# wifi_lora_gw_v1_1.net
KiCad netlist of a schematic drawn in EAGLE
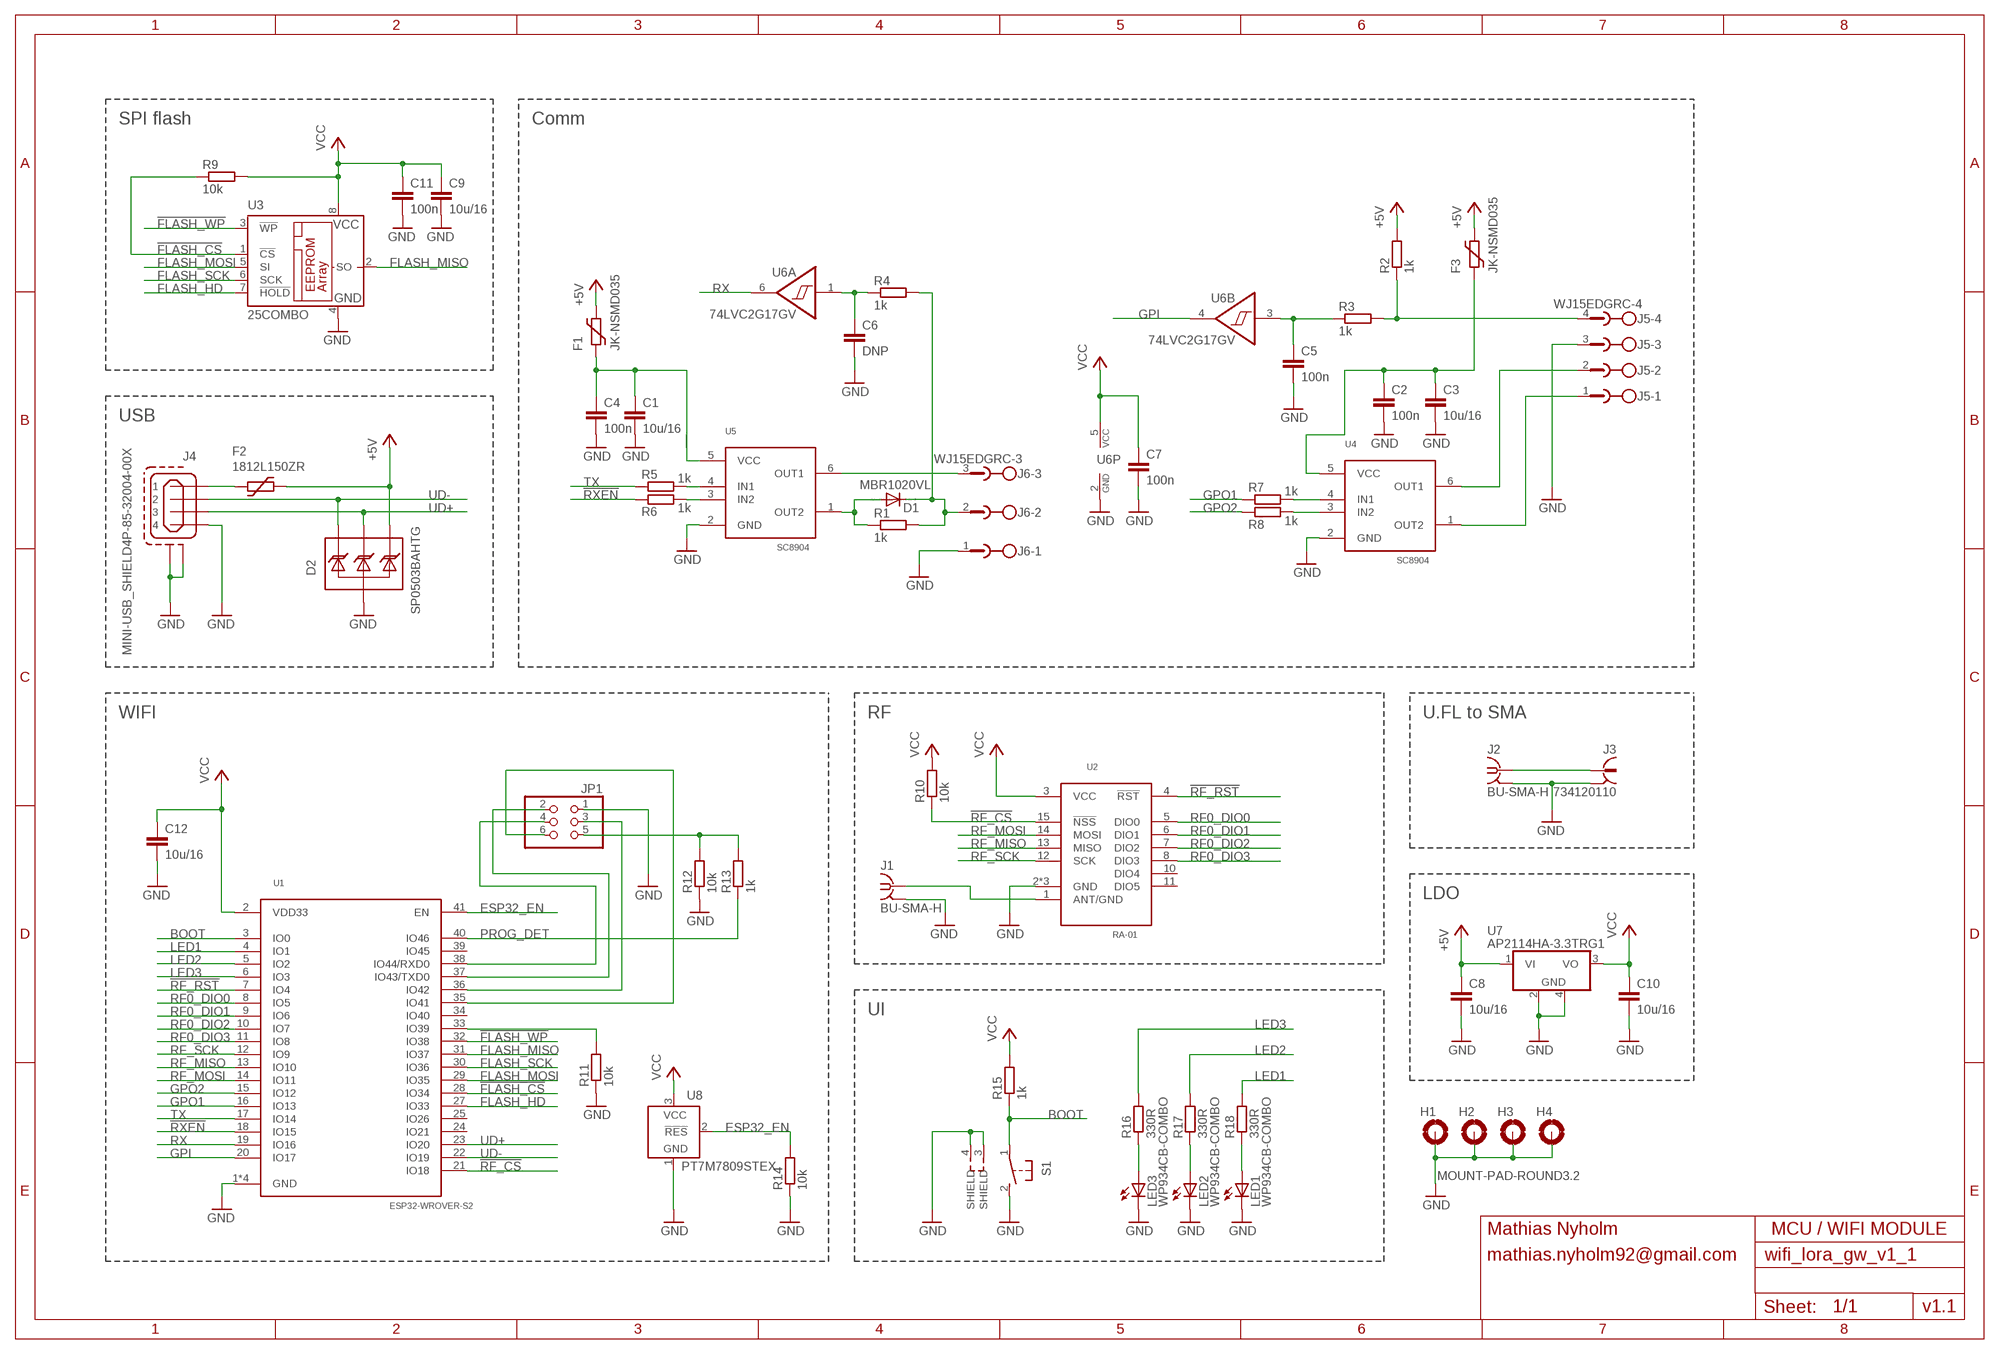
[diagram p0: schematic, sheet 1]

(export (version "E")
  (design (tool "Eeschema 10.0.6"))
  (components
    (comp (ref "C1")
      (value "10u/16")
      (footprint "eagle-import:C1206")
      (libsource (lib "eagle-import") (part "C-EUC1206"))
    )
    (comp (ref "C2")
      (value "100n")
      (footprint "eagle-import:C0805")
      (libsource (lib "eagle-import") (part "C-EUC0805"))
    )
    (comp (ref "C3")
      (value "10u/16")
      (footprint "eagle-import:C1206")
      (libsource (lib "eagle-import") (part "C-EUC1206"))
    )
    (comp (ref "C4")
      (value "100n")
      (footprint "eagle-import:C0805")
      (libsource (lib "eagle-import") (part "C-EUC0805"))
    )
    (comp (ref "C5")
      (value "100n")
      (footprint "eagle-import:C0805")
      (libsource (lib "eagle-import") (part "C-EUC0805"))
    )
    (comp (ref "C6")
      (value "DNP")
      (footprint "eagle-import:C0805")
      (libsource (lib "eagle-import") (part "C-EUC0805"))
    )
    (comp (ref "C7")
      (value "100n")
      (footprint "eagle-import:C0805")
      (libsource (lib "eagle-import") (part "C-EUC0805"))
    )
    (comp (ref "C8")
      (value "10u/16")
      (footprint "eagle-import:C1206")
      (libsource (lib "eagle-import") (part "C-EUC1206"))
    )
    (comp (ref "C9")
      (value "10u/16")
      (footprint "eagle-import:C1206")
      (libsource (lib "eagle-import") (part "C-EUC1206"))
    )
    (comp (ref "C10")
      (value "10u/16")
      (footprint "eagle-import:C1206")
      (libsource (lib "eagle-import") (part "C-EUC1206"))
    )
    (comp (ref "C11")
      (value "100n")
      (footprint "eagle-import:C0805")
      (libsource (lib "eagle-import") (part "C-EUC0805"))
    )
    (comp (ref "C12")
      (value "10u/16")
      (footprint "eagle-import:C1206")
      (libsource (lib "eagle-import") (part "C-EUC1206"))
    )
    (comp (ref "D1")
      (value "MBR1020VL")
      (footprint "eagle-import:SOD123")
      (libsource (lib "eagle-import") (part "DIODE-SOD123"))
    )
    (comp (ref "D2")
      (value "SP0503BAHTG")
      (footprint "eagle-import:SOT143")
      (libsource (lib "eagle-import") (part "SP0503BAHTG"))
    )
    (comp (ref "F1")
      (value "JK-NSMD035")
      (footprint "eagle-import:1206L")
      (libsource (lib "eagle-import") (part "1206L"))
    )
    (comp (ref "F2")
      (value "1812L150ZR")
      (footprint "eagle-import:1812L")
      (libsource (lib "eagle-import") (part "1812L"))
    )
    (comp (ref "F3")
      (value "JK-NSMD035")
      (footprint "eagle-import:1206L")
      (libsource (lib "eagle-import") (part "1206L"))
    )
    (comp (ref "H1")
      (value "MOUNT-PAD-ROUND3.2")
      (footprint "eagle-import:3,2-PAD")
      (libsource (lib "eagle-import") (part "MOUNT-PAD-ROUND3.2"))
    )
    (comp (ref "H2")
      (value "MOUNT-PAD-ROUND3.2")
      (footprint "eagle-import:3,2-PAD")
      (libsource (lib "eagle-import") (part "MOUNT-PAD-ROUND3.2"))
    )
    (comp (ref "H3")
      (value "MOUNT-PAD-ROUND3.2")
      (footprint "eagle-import:3,2-PAD")
      (libsource (lib "eagle-import") (part "MOUNT-PAD-ROUND3.2"))
    )
    (comp (ref "H4")
      (value "MOUNT-PAD-ROUND3.2")
      (footprint "eagle-import:3,2-PAD")
      (libsource (lib "eagle-import") (part "MOUNT-PAD-ROUND3.2"))
    )
    (comp (ref "J1")
      (value "BU-SMA-H")
      (footprint "eagle-import:BU-SMA-H")
      (libsource (lib "eagle-import") (part "BU-SMA-H"))
    )
    (comp (ref "J2")
      (value "BU-SMA-H")
      (footprint "eagle-import:BU-SMA-H")
      (libsource (lib "eagle-import") (part "BU-SMA-H"))
    )
    (comp (ref "J3")
      (value "734120110")
      (footprint "eagle-import:734120110")
      (libsource (lib "eagle-import") (part "734120110"))
    )
    (comp (ref "J4")
      (value "MINI-USB_SHIELD4P-85-32004-00X")
      (footprint "eagle-import:85-32004-00X")
      (libsource (lib "eagle-import") (part "MINI-USB_SHIELD4P-85-32004-00X"))
    )
    (comp (ref "J5")
      (value "WJ15EDGRC-4")
      (footprint "eagle-import:WJ15EDGRC-3.81-4")
      (libsource (lib "eagle-import") (part "WJ15EDGRC-4"))
    )
    (comp (ref "J6")
      (value "WJ15EDGRC-3")
      (footprint "eagle-import:WJ15EDGRC-3.81-3")
      (libsource (lib "eagle-import") (part "WJ15EDGRC-3"))
    )
    (comp (ref "JP1")
      (value "PINHD-2X3")
      (footprint "eagle-import:2X03")
      (libsource (lib "eagle-import") (part "PINHD-2X3"))
    )
    (comp (ref "LED1")
      (value "WP934CB-COMBO")
      (footprint "eagle-import:WP934CB-COMBO")
      (libsource (lib "eagle-import") (part "WP934CB-COMBO"))
    )
    (comp (ref "LED2")
      (value "WP934CB-COMBO")
      (footprint "eagle-import:WP934CB-COMBO")
      (libsource (lib "eagle-import") (part "WP934CB-COMBO"))
    )
    (comp (ref "LED3")
      (value "WP934CB-COMBO")
      (footprint "eagle-import:WP934CB-COMBO")
      (libsource (lib "eagle-import") (part "WP934CB-COMBO"))
    )
    (comp (ref "R1")
      (value "1k")
      (footprint "eagle-import:R0805")
      (libsource (lib "eagle-import") (part "R-EU_R0805"))
    )
    (comp (ref "R2")
      (value "1k")
      (footprint "eagle-import:R0805")
      (libsource (lib "eagle-import") (part "R-EU_R0805"))
    )
    (comp (ref "R3")
      (value "1k")
      (footprint "eagle-import:R0805")
      (libsource (lib "eagle-import") (part "R-EU_R0805"))
    )
    (comp (ref "R4")
      (value "1k")
      (footprint "eagle-import:R0805")
      (libsource (lib "eagle-import") (part "R-EU_R0805"))
    )
    (comp (ref "R5")
      (value "1k")
      (footprint "eagle-import:R0805")
      (libsource (lib "eagle-import") (part "R-EU_R0805"))
    )
    (comp (ref "R6")
      (value "1k")
      (footprint "eagle-import:R0805")
      (libsource (lib "eagle-import") (part "R-EU_R0805"))
    )
    (comp (ref "R7")
      (value "1k")
      (footprint "eagle-import:R0805")
      (libsource (lib "eagle-import") (part "R-EU_R0805"))
    )
    (comp (ref "R8")
      (value "1k")
      (footprint "eagle-import:R0805")
      (libsource (lib "eagle-import") (part "R-EU_R0805"))
    )
    (comp (ref "R9")
      (value "10k")
      (footprint "eagle-import:R0805")
      (libsource (lib "eagle-import") (part "R-EU_R0805"))
    )
    (comp (ref "R10")
      (value "10k")
      (footprint "eagle-import:R0805")
      (libsource (lib "eagle-import") (part "R-EU_R0805"))
    )
    (comp (ref "R11")
      (value "10k")
      (footprint "eagle-import:R0805")
      (libsource (lib "eagle-import") (part "R-EU_R0805"))
    )
    (comp (ref "R12")
      (value "10k")
      (footprint "eagle-import:R0805")
      (libsource (lib "eagle-import") (part "R-EU_R0805"))
    )
    (comp (ref "R13")
      (value "1k")
      (footprint "eagle-import:R0805")
      (libsource (lib "eagle-import") (part "R-EU_R0805"))
    )
    (comp (ref "R14")
      (value "10k")
      (footprint "eagle-import:R0805")
      (libsource (lib "eagle-import") (part "R-EU_R0805"))
    )
    (comp (ref "R15")
      (value "1k")
      (footprint "eagle-import:R0805")
      (libsource (lib "eagle-import") (part "R-EU_R0805"))
    )
    (comp (ref "R16")
      (value "330R")
      (footprint "eagle-import:R0805")
      (libsource (lib "eagle-import") (part "R-EU_R0805"))
    )
    (comp (ref "R17")
      (value "330R")
      (footprint "eagle-import:R0805")
      (libsource (lib "eagle-import") (part "R-EU_R0805"))
    )
    (comp (ref "R18")
      (value "330R")
      (footprint "eagle-import:R0805")
      (libsource (lib "eagle-import") (part "R-EU_R0805"))
    )
    (comp (ref "S1")
      (value "31-XX")
      (footprint "eagle-import:B3F-31XX")
      (libsource (lib "eagle-import") (part "31-XX"))
    )
    (comp (ref "U1")
      (value "ESP32-WROVER-S2")
      (footprint "eagle-import:ESP32-WROVER-I-S2")
      (libsource (lib "eagle-import") (part "ESP32-WROVER-S2"))
    )
    (comp (ref "U2")
      (value "RA-01")
      (footprint "eagle-import:RA-02")
      (libsource (lib "eagle-import") (part "RA-02"))
    )
    (comp (ref "U3")
      (value "25COMBO")
      (footprint "eagle-import:SO-08M-COMBO")
      (libsource (lib "eagle-import") (part "25COMBO"))
    )
    (comp (ref "U4")
      (value "SC8904")
      (footprint "eagle-import:SOT23-6L")
      (libsource (lib "eagle-import") (part "SC8904"))
    )
    (comp (ref "U5")
      (value "SC8904")
      (footprint "eagle-import:SOT23-6L")
      (libsource (lib "eagle-import") (part "SC8904"))
    )
    (comp (ref "U6")
      (value "74LVC2G17GV")
      (footprint "eagle-import:SOT23-6L")
      (libsource (lib "eagle-import") (part "74LVC2G17GV"))
    )
    (comp (ref "U7")
      (value "AP2114HA-3.3TRG1")
      (footprint "eagle-import:SOT223")
      (libsource (lib "eagle-import") (part "MCP1754-DB"))
    )
    (comp (ref "U8")
      (value "PT7M7809STEX")
      (footprint "eagle-import:SOT23B-3")
      (libsource (lib "eagle-import") (part "APX809S-SA"))
    )
  )
  (nets
    (net (code "1") (name "+5V") (class "Default")
      (node (ref "C8") (pin "1") (pinfunction "1_1") (pintype "passive"))
      (node (ref "D2") (pin "4") (pinfunction "C3_4") (pintype "passive"))
      (node (ref "F1") (pin "P$2") (pinfunction "2_P$2") (pintype "passive"))
      (node (ref "F2") (pin "P$2") (pinfunction "2_P$2") (pintype "passive"))
      (node (ref "F3") (pin "P$2") (pinfunction "2_P$2") (pintype "passive"))
      (node (ref "R2") (pin "2") (pinfunction "2_2") (pintype "passive"))
      (node (ref "U7") (pin "1") (pinfunction "VI_1") (pintype "input"))
    )
    (net (code "2") (name "/BOOT") (class "Default")
      (node (ref "R15") (pin "1") (pinfunction "1_1") (pintype "passive"))
      (node (ref "S1") (pin "1") (pinfunction "P_1") (pintype "passive"))
      (node (ref "U1") (pin "3") (pinfunction "IO0_3") (pintype "bidirectional"))
    )
    (net (code "3") (name "/ESP32_EN") (class "Default")
      (node (ref "R14") (pin "2") (pinfunction "2_2") (pintype "passive"))
      (node (ref "U1") (pin "41") (pinfunction "EN_41") (pintype "bidirectional"))
      (node (ref "U8") (pin "2") (pinfunction "~{RES}_2") (pintype "output"))
    )
    (net (code "4") (name "/FLASH_HD") (class "Default")
      (node (ref "U1") (pin "27") (pinfunction "IO33_27") (pintype "bidirectional"))
      (node (ref "U3") (pin "7") (pinfunction "~{HOLD}_7") (pintype "input"))
    )
    (net (code "5") (name "/FLASH_MISO") (class "Default")
      (node (ref "U1") (pin "31") (pinfunction "IO37_31") (pintype "bidirectional"))
      (node (ref "U3") (pin "2") (pinfunction "SO_2") (pintype "bidirectional"))
    )
    (net (code "6") (name "/FLASH_MOSI") (class "Default")
      (node (ref "U1") (pin "29") (pinfunction "IO35_29") (pintype "bidirectional"))
      (node (ref "U3") (pin "5") (pinfunction "SI_5") (pintype "input"))
    )
    (net (code "7") (name "/FLASH_SCK") (class "Default")
      (node (ref "U1") (pin "30") (pinfunction "IO36_30") (pintype "bidirectional"))
      (node (ref "U3") (pin "6") (pinfunction "SCK_6") (pintype "input"))
    )
    (net (code "8") (name "/GPI") (class "Default")
      (node (ref "U1") (pin "20") (pinfunction "IO17_20") (pintype "bidirectional"))
      (node (ref "U6") (pin "4") (pinfunction "O_4") (pintype "output"))
    )
    (net (code "9") (name "/GPO1") (class "Default")
      (node (ref "R7") (pin "1") (pinfunction "1_1") (pintype "passive"))
      (node (ref "U1") (pin "16") (pinfunction "IO13_16") (pintype "bidirectional"))
    )
    (net (code "10") (name "/GPO2") (class "Default")
      (node (ref "R8") (pin "1") (pinfunction "1_1") (pintype "passive"))
      (node (ref "U1") (pin "15") (pinfunction "IO12_15") (pintype "bidirectional"))
    )
    (net (code "11") (name "/LED1") (class "Default")
      (node (ref "R18") (pin "2") (pinfunction "2_2") (pintype "passive"))
      (node (ref "U1") (pin "4") (pinfunction "IO1_4") (pintype "bidirectional"))
    )
    (net (code "12") (name "/LED2") (class "Default")
      (node (ref "R17") (pin "2") (pinfunction "2_2") (pintype "passive"))
      (node (ref "U1") (pin "5") (pinfunction "IO2_5") (pintype "bidirectional"))
    )
    (net (code "13") (name "/LED3") (class "Default")
      (node (ref "R16") (pin "2") (pinfunction "2_2") (pintype "passive"))
      (node (ref "U1") (pin "6") (pinfunction "IO3_6") (pintype "bidirectional"))
    )
    (net (code "14") (name "/PROG_DET") (class "Default")
      (node (ref "R13") (pin "1") (pinfunction "1_1") (pintype "passive"))
      (node (ref "U1") (pin "40") (pinfunction "IO46_40") (pintype "bidirectional"))
    )
    (net (code "15") (name "/RF0_DIO0") (class "Default")
      (node (ref "U1") (pin "8") (pinfunction "IO5_8") (pintype "bidirectional"))
      (node (ref "U2") (pin "5") (pinfunction "DIO0_5") (pintype "bidirectional"))
    )
    (net (code "16") (name "/RF0_DIO1") (class "Default")
      (node (ref "U1") (pin "9") (pinfunction "IO6_9") (pintype "bidirectional"))
      (node (ref "U2") (pin "6") (pinfunction "DIO1_6") (pintype "bidirectional"))
    )
    (net (code "17") (name "/RF0_DIO2") (class "Default")
      (node (ref "U1") (pin "10") (pinfunction "IO7_10") (pintype "bidirectional"))
      (node (ref "U2") (pin "7") (pinfunction "DIO2_7") (pintype "bidirectional"))
    )
    (net (code "18") (name "/RF0_DIO3") (class "Default")
      (node (ref "U1") (pin "11") (pinfunction "IO8_11") (pintype "bidirectional"))
      (node (ref "U2") (pin "8") (pinfunction "DIO3_8") (pintype "bidirectional"))
    )
    (net (code "19") (name "/RF_MISO") (class "Default")
      (node (ref "U1") (pin "13") (pinfunction "IO10_13") (pintype "bidirectional"))
      (node (ref "U2") (pin "13") (pinfunction "MISO_13") (pintype "bidirectional"))
    )
    (net (code "20") (name "/RF_MOSI") (class "Default")
      (node (ref "U1") (pin "14") (pinfunction "IO11_14") (pintype "bidirectional"))
      (node (ref "U2") (pin "14") (pinfunction "MOSI_14") (pintype "bidirectional"))
    )
    (net (code "21") (name "/RF_SCK") (class "Default")
      (node (ref "U1") (pin "12") (pinfunction "IO9_12") (pintype "bidirectional"))
      (node (ref "U2") (pin "12") (pinfunction "SCK_12") (pintype "bidirectional"))
    )
    (net (code "22") (name "/RX") (class "Default")
      (node (ref "U1") (pin "19") (pinfunction "IO16_19") (pintype "bidirectional"))
      (node (ref "U6") (pin "6") (pinfunction "O_6") (pintype "output"))
    )
    (net (code "23") (name "/TX") (class "Default")
      (node (ref "R5") (pin "1") (pinfunction "1_1") (pintype "passive"))
      (node (ref "U1") (pin "17") (pinfunction "IO14_17") (pintype "bidirectional"))
    )
    (net (code "24") (name "/UD+") (class "Default")
      (node (ref "D2") (pin "3") (pinfunction "C2_3") (pintype "passive"))
      (node (ref "J4") (pin "3") (pinfunction "3_3") (pintype "passive"))
      (node (ref "U1") (pin "23") (pinfunction "IO20_23") (pintype "bidirectional"))
    )
    (net (code "25") (name "/UD-") (class "Default")
      (node (ref "D2") (pin "2") (pinfunction "C1_2") (pintype "passive"))
      (node (ref "J4") (pin "2") (pinfunction "2_2") (pintype "passive"))
      (node (ref "U1") (pin "22") (pinfunction "IO19_22") (pintype "bidirectional"))
    )
    (net (code "26") (name "/~{FLASH_CS}") (class "Default")
      (node (ref "R9") (pin "1") (pinfunction "1_1") (pintype "passive"))
      (node (ref "U1") (pin "28") (pinfunction "IO34_28") (pintype "bidirectional"))
      (node (ref "U3") (pin "1") (pinfunction "~{CS}_1") (pintype "input"))
    )
    (net (code "27") (name "/~{FLASH_WP}") (class "Default")
      (node (ref "U1") (pin "32") (pinfunction "IO38_32") (pintype "bidirectional"))
      (node (ref "U3") (pin "3") (pinfunction "~{WP}_3") (pintype "input"))
    )
    (net (code "28") (name "/~{RF_CS}") (class "Default")
      (node (ref "R10") (pin "1") (pinfunction "1_1") (pintype "passive"))
      (node (ref "U1") (pin "21") (pinfunction "IO18_21") (pintype "bidirectional"))
      (node (ref "U2") (pin "15") (pinfunction "~{NSS}_15") (pintype "bidirectional"))
    )
    (net (code "29") (name "/~{RF_RST}") (class "Default")
      (node (ref "U1") (pin "7") (pinfunction "IO4_7") (pintype "bidirectional"))
      (node (ref "U2") (pin "4") (pinfunction "~{RST}_4") (pintype "bidirectional"))
    )
    (net (code "30") (name "/~{RXEN}") (class "Default")
      (node (ref "R6") (pin "1") (pinfunction "1_1") (pintype "passive"))
      (node (ref "U1") (pin "18") (pinfunction "IO15_18") (pintype "bidirectional"))
    )
    (net (code "31") (name "GND") (class "Default")
      (node (ref "C1") (pin "2") (pinfunction "2_2") (pintype "passive"))
      (node (ref "C10") (pin "2") (pinfunction "2_2") (pintype "passive"))
      (node (ref "C11") (pin "2") (pinfunction "2_2") (pintype "passive"))
      (node (ref "C12") (pin "2") (pinfunction "2_2") (pintype "passive"))
      (node (ref "C2") (pin "2") (pinfunction "2_2") (pintype "passive"))
      (node (ref "C3") (pin "2") (pinfunction "2_2") (pintype "passive"))
      (node (ref "C4") (pin "2") (pinfunction "2_2") (pintype "passive"))
      (node (ref "C5") (pin "2") (pinfunction "2_2") (pintype "passive"))
      (node (ref "C6") (pin "2") (pinfunction "2_2") (pintype "passive"))
      (node (ref "C7") (pin "2") (pinfunction "2_2") (pintype "passive"))
      (node (ref "C8") (pin "2") (pinfunction "2_2") (pintype "passive"))
      (node (ref "C9") (pin "2") (pinfunction "2_2") (pintype "passive"))
      (node (ref "D2") (pin "1") (pinfunction "A_1") (pintype "passive"))
      (node (ref "H1") (pin "B3,2") (pinfunction "MOUNT_B3,2") (pintype "passive"))
      (node (ref "H2") (pin "B3,2") (pinfunction "MOUNT_B3,2") (pintype "passive"))
      (node (ref "H3") (pin "B3,2") (pinfunction "MOUNT_B3,2") (pintype "passive"))
      (node (ref "H4") (pin "B3,2") (pinfunction "MOUNT_B3,2") (pintype "passive"))
      (node (ref "J1") (pin "2") (pinfunction "GND_2") (pintype "power_in"))
      (node (ref "J2") (pin "2") (pinfunction "GND_2") (pintype "power_in"))
      (node (ref "J3") (pin "S@1") (pinfunction "2_S@1") (pintype "passive"))
      (node (ref "J3") (pin "S@2") (pinfunction "2_S@2") (pintype "passive"))
      (node (ref "J3") (pin "S@3") (pinfunction "2_S@3") (pintype "passive"))
      (node (ref "J4") (pin "4") (pinfunction "4_4") (pintype "passive"))
      (node (ref "J4") (pin "M1") (pinfunction "S1_M1") (pintype "passive"))
      (node (ref "J4") (pin "M2") (pinfunction "S2_M2") (pintype "passive"))
      (node (ref "J5") (pin "3") (pinfunction "1_3") (pintype "passive"))
      (node (ref "J6") (pin "1") (pinfunction "1_1") (pintype "passive"))
      (node (ref "JP1") (pin "1") (pinfunction "1_1") (pintype "passive"))
      (node (ref "LED1") (pin "K") (pinfunction "C_K") (pintype "passive"))
      (node (ref "LED1") (pin "K1") (pinfunction "C_K1") (pintype "passive"))
      (node (ref "LED2") (pin "K") (pinfunction "C_K") (pintype "passive"))
      (node (ref "LED2") (pin "K1") (pinfunction "C_K1") (pintype "passive"))
      (node (ref "LED3") (pin "K") (pinfunction "C_K") (pintype "passive"))
      (node (ref "LED3") (pin "K1") (pinfunction "C_K1") (pintype "passive"))
      (node (ref "R11") (pin "1") (pinfunction "1_1") (pintype "passive"))
      (node (ref "R12") (pin "1") (pinfunction "1_1") (pintype "passive"))
      (node (ref "R14") (pin "1") (pinfunction "1_1") (pintype "passive"))
      (node (ref "S1") (pin "2") (pinfunction "S_2") (pintype "passive"))
      (node (ref "S1") (pin "3") (pinfunction "SHIELD_3") (pintype "passive"))
      (node (ref "S1") (pin "4") (pinfunction "SHIELD_4") (pintype "passive"))
      (node (ref "U1") (pin "1") (pinfunction "GND_1") (pintype "bidirectional"))
      (node (ref "U1") (pin "26") (pinfunction "GND_26") (pintype "bidirectional"))
      (node (ref "U1") (pin "42") (pinfunction "GND_42") (pintype "bidirectional"))
      (node (ref "U1") (pin "43") (pinfunction "GND_43") (pintype "bidirectional"))
      (node (ref "U2") (pin "16") (pinfunction "GND_16") (pintype "bidirectional"))
      (node (ref "U2") (pin "2") (pinfunction "GND_2") (pintype "bidirectional"))
      (node (ref "U2") (pin "9") (pinfunction "GND_9") (pintype "bidirectional"))
      (node (ref "U3") (pin "4") (pinfunction "GND_4") (pintype "power_in"))
      (node (ref "U4") (pin "2") (pinfunction "GND_2") (pintype "bidirectional"))
      (node (ref "U5") (pin "2") (pinfunction "GND_2") (pintype "bidirectional"))
      (node (ref "U6") (pin "2") (pinfunction "GND_2") (pintype "power_in"))
      (node (ref "U7") (pin "2") (pinfunction "GND_2") (pintype "passive"))
      (node (ref "U7") (pin "4") (pinfunction "GND_4") (pintype "passive"))
      (node (ref "U8") (pin "1") (pinfunction "GND_1") (pintype "power_in"))
    )
    (net (code "32") (name "Net-(F1-1)") (class "Default")
      (node (ref "C1") (pin "1") (pinfunction "1_1") (pintype "passive"))
      (node (ref "C4") (pin "1") (pinfunction "1_1") (pintype "passive"))
      (node (ref "F1") (pin "P$1") (pinfunction "1_P$1") (pintype "passive"))
      (node (ref "U5") (pin "5") (pinfunction "VCC_5") (pintype "bidirectional"))
    )
    (net (code "33") (name "Net-(F2-1)") (class "Default")
      (node (ref "F2") (pin "P$1") (pinfunction "1_P$1") (pintype "passive"))
      (node (ref "J4") (pin "1") (pinfunction "1_1") (pintype "passive"))
    )
    (net (code "34") (name "Net-(F3-1)") (class "Default")
      (node (ref "C2") (pin "1") (pinfunction "1_1") (pintype "passive"))
      (node (ref "C3") (pin "1") (pinfunction "1_1") (pintype "passive"))
      (node (ref "F3") (pin "P$1") (pinfunction "1_P$1") (pintype "passive"))
      (node (ref "U4") (pin "5") (pinfunction "VCC_5") (pintype "bidirectional"))
    )
    (net (code "35") (name "Net-(J2-Pad1)") (class "Default")
      (node (ref "J2") (pin "1") (pinfunction "1_1") (pintype "passive"))
      (node (ref "J3") (pin "1") (pinfunction "1_1") (pintype "passive"))
    )
    (net (code "36") (name "Net-(J5B-1)") (class "Default")
      (node (ref "J5") (pin "2") (pinfunction "1_2") (pintype "passive"))
      (node (ref "U4") (pin "6") (pinfunction "OUT1_6") (pintype "output"))
    )
    (net (code "37") (name "Net-(J5D-1)") (class "Default")
      (node (ref "J5") (pin "4") (pinfunction "1_4") (pintype "passive"))
      (node (ref "R2") (pin "1") (pinfunction "1_1") (pintype "passive"))
      (node (ref "R3") (pin "2") (pinfunction "2_2") (pintype "passive"))
    )
    (net (code "38") (name "Net-(J6B-1)") (class "Default")
      (node (ref "D1") (pin "C") (pinfunction "C_C") (pintype "passive"))
      (node (ref "J6") (pin "2") (pinfunction "1_2") (pintype "passive"))
      (node (ref "R1") (pin "2") (pinfunction "2_2") (pintype "passive"))
      (node (ref "R4") (pin "2") (pinfunction "2_2") (pintype "passive"))
    )
    (net (code "39") (name "Net-(J6C-1)") (class "Default")
      (node (ref "J6") (pin "3") (pinfunction "1_3") (pintype "passive"))
      (node (ref "U5") (pin "6") (pinfunction "OUT1_6") (pintype "output"))
    )
    (net (code "40") (name "Net-(JP1-Pad5)") (class "Default")
      (node (ref "JP1") (pin "5") (pinfunction "5_5") (pintype "passive"))
      (node (ref "R12") (pin "2") (pinfunction "2_2") (pintype "passive"))
      (node (ref "R13") (pin "2") (pinfunction "2_2") (pintype "passive"))
    )
    (net (code "41") (name "Net-(LED1-A-PadA1)") (class "Default")
      (node (ref "LED1") (pin "A") (pinfunction "A_A") (pintype "passive"))
      (node (ref "LED1") (pin "A1") (pinfunction "A_A1") (pintype "passive"))
      (node (ref "R18") (pin "1") (pinfunction "1_1") (pintype "passive"))
    )
    (net (code "42") (name "Net-(LED2-A-PadA1)") (class "Default")
      (node (ref "LED2") (pin "A") (pinfunction "A_A") (pintype "passive"))
      (node (ref "LED2") (pin "A1") (pinfunction "A_A1") (pintype "passive"))
      (node (ref "R17") (pin "1") (pinfunction "1_1") (pintype "passive"))
    )
    (net (code "43") (name "Net-(LED3-A-PadA1)") (class "Default")
      (node (ref "LED3") (pin "A") (pinfunction "A_A") (pintype "passive"))
      (node (ref "LED3") (pin "A1") (pinfunction "A_A1") (pintype "passive"))
      (node (ref "R16") (pin "1") (pinfunction "1_1") (pintype "passive"))
    )
    (net (code "44") (name "Net-(U1-IO39)") (class "Default")
      (node (ref "R11") (pin "2") (pinfunction "2_2") (pintype "passive"))
      (node (ref "U1") (pin "33") (pinfunction "IO39_33") (pintype "bidirectional"))
    )
    (net (code "45") (name "Net-(U1-IO41)") (class "Default")
      (node (ref "JP1") (pin "6") (pinfunction "6_6") (pintype "passive"))
      (node (ref "U1") (pin "35") (pinfunction "IO41_35") (pintype "bidirectional"))
    )
    (net (code "46") (name "Net-(U1-IO42)") (class "Default")
      (node (ref "JP1") (pin "3") (pinfunction "3_3") (pintype "passive"))
      (node (ref "U1") (pin "36") (pinfunction "IO42_36") (pintype "bidirectional"))
    )
    (net (code "47") (name "Net-(U1-IO43{slash}TXD0)") (class "Default")
      (node (ref "JP1") (pin "2") (pinfunction "2_2") (pintype "passive"))
      (node (ref "U1") (pin "37") (pinfunction "IO43/TXD0_37") (pintype "bidirectional"))
    )
    (net (code "48") (name "Net-(U1-IO44{slash}RXD0)") (class "Default")
      (node (ref "JP1") (pin "4") (pinfunction "4_4") (pintype "passive"))
      (node (ref "U1") (pin "38") (pinfunction "IO44/RXD0_38") (pintype "bidirectional"))
    )
    (net (code "49") (name "Net-(U2-ANT{slash}GND)") (class "Default")
      (node (ref "J1") (pin "1") (pinfunction "1_1") (pintype "passive"))
      (node (ref "U2") (pin "1") (pinfunction "ANT/GND_1") (pintype "bidirectional"))
    )
    (net (code "50") (name "Net-(U4-IN1)") (class "Default")
      (node (ref "R7") (pin "2") (pinfunction "2_2") (pintype "passive"))
      (node (ref "U4") (pin "4") (pinfunction "IN1_4") (pintype "input"))
    )
    (net (code "51") (name "Net-(U4-IN2)") (class "Default")
      (node (ref "R8") (pin "2") (pinfunction "2_2") (pintype "passive"))
      (node (ref "U4") (pin "3") (pinfunction "IN2_3") (pintype "input"))
    )
    (net (code "52") (name "Net-(U4-OUT2)") (class "Default")
      (node (ref "J5") (pin "1") (pinfunction "1_1") (pintype "passive"))
      (node (ref "U4") (pin "1") (pinfunction "OUT2_1") (pintype "output"))
    )
    (net (code "53") (name "Net-(U5-IN1)") (class "Default")
      (node (ref "R5") (pin "2") (pinfunction "2_2") (pintype "passive"))
      (node (ref "U5") (pin "4") (pinfunction "IN1_4") (pintype "input"))
    )
    (net (code "54") (name "Net-(U5-IN2)") (class "Default")
      (node (ref "R6") (pin "2") (pinfunction "2_2") (pintype "passive"))
      (node (ref "U5") (pin "3") (pinfunction "IN2_3") (pintype "input"))
    )
    (net (code "55") (name "Net-(U5-OUT2)") (class "Default")
      (node (ref "D1") (pin "A") (pinfunction "A_A") (pintype "passive"))
      (node (ref "R1") (pin "1") (pinfunction "1_1") (pintype "passive"))
      (node (ref "U5") (pin "1") (pinfunction "OUT2_1") (pintype "output"))
    )
    (net (code "56") (name "Net-(U6A-I)") (class "Default")
      (node (ref "C6") (pin "1") (pinfunction "1_1") (pintype "passive"))
      (node (ref "R4") (pin "1") (pinfunction "1_1") (pintype "passive"))
      (node (ref "U6") (pin "1") (pinfunction "I_1") (pintype "input"))
    )
    (net (code "57") (name "Net-(U6B-I)") (class "Default")
      (node (ref "C5") (pin "1") (pinfunction "1_1") (pintype "passive"))
      (node (ref "R3") (pin "1") (pinfunction "1_1") (pintype "passive"))
      (node (ref "U6") (pin "3") (pinfunction "I_3") (pintype "input"))
    )
    (net (code "58") (name "VCC") (class "Default")
      (node (ref "C10") (pin "1") (pinfunction "1_1") (pintype "passive"))
      (node (ref "C11") (pin "1") (pinfunction "1_1") (pintype "passive"))
      (node (ref "C12") (pin "1") (pinfunction "1_1") (pintype "passive"))
      (node (ref "C7") (pin "1") (pinfunction "1_1") (pintype "passive"))
      (node (ref "C9") (pin "1") (pinfunction "1_1") (pintype "passive"))
      (node (ref "R10") (pin "2") (pinfunction "2_2") (pintype "passive"))
      (node (ref "R15") (pin "2") (pinfunction "2_2") (pintype "passive"))
      (node (ref "R9") (pin "2") (pinfunction "2_2") (pintype "passive"))
      (node (ref "U1") (pin "2") (pinfunction "VDD33_2") (pintype "bidirectional"))
      (node (ref "U2") (pin "3") (pinfunction "VCC_3") (pintype "bidirectional"))
      (node (ref "U3") (pin "8") (pinfunction "VCC_8") (pintype "power_in"))
      (node (ref "U6") (pin "5") (pinfunction "VCC_5") (pintype "power_in"))
      (node (ref "U7") (pin "3") (pinfunction "VO_3") (pintype "passive"))
      (node (ref "U8") (pin "3") (pinfunction "VCC_3") (pintype "power_in"))
    )
    (net (code "59") (name "unconnected-(U1-IO21-Pad24)") (class "Default")
      (node (ref "U1") (pin "24") (pinfunction "IO21_24") (pintype "bidirectional"))
    )
    (net (code "60") (name "unconnected-(U1-IO26-Pad25)") (class "Default")
      (node (ref "U1") (pin "25") (pinfunction "IO26_25") (pintype "bidirectional"))
    )
    (net (code "61") (name "unconnected-(U1-IO40-Pad34)") (class "Default")
      (node (ref "U1") (pin "34") (pinfunction "IO40_34") (pintype "bidirectional"))
    )
    (net (code "62") (name "unconnected-(U1-IO45-Pad39)") (class "Default")
      (node (ref "U1") (pin "39") (pinfunction "IO45_39") (pintype "bidirectional"))
    )
    (net (code "63") (name "unconnected-(U2-DIO4-Pad10)") (class "Default")
      (node (ref "U2") (pin "10") (pinfunction "DIO4_10") (pintype "bidirectional"))
    )
    (net (code "64") (name "unconnected-(U2-DIO5-Pad11)") (class "Default")
      (node (ref "U2") (pin "11") (pinfunction "DIO5_11") (pintype "bidirectional"))
    )
  )
)
